# mymote-logger.net
KiCad netlist of a schematic drawn in EAGLE
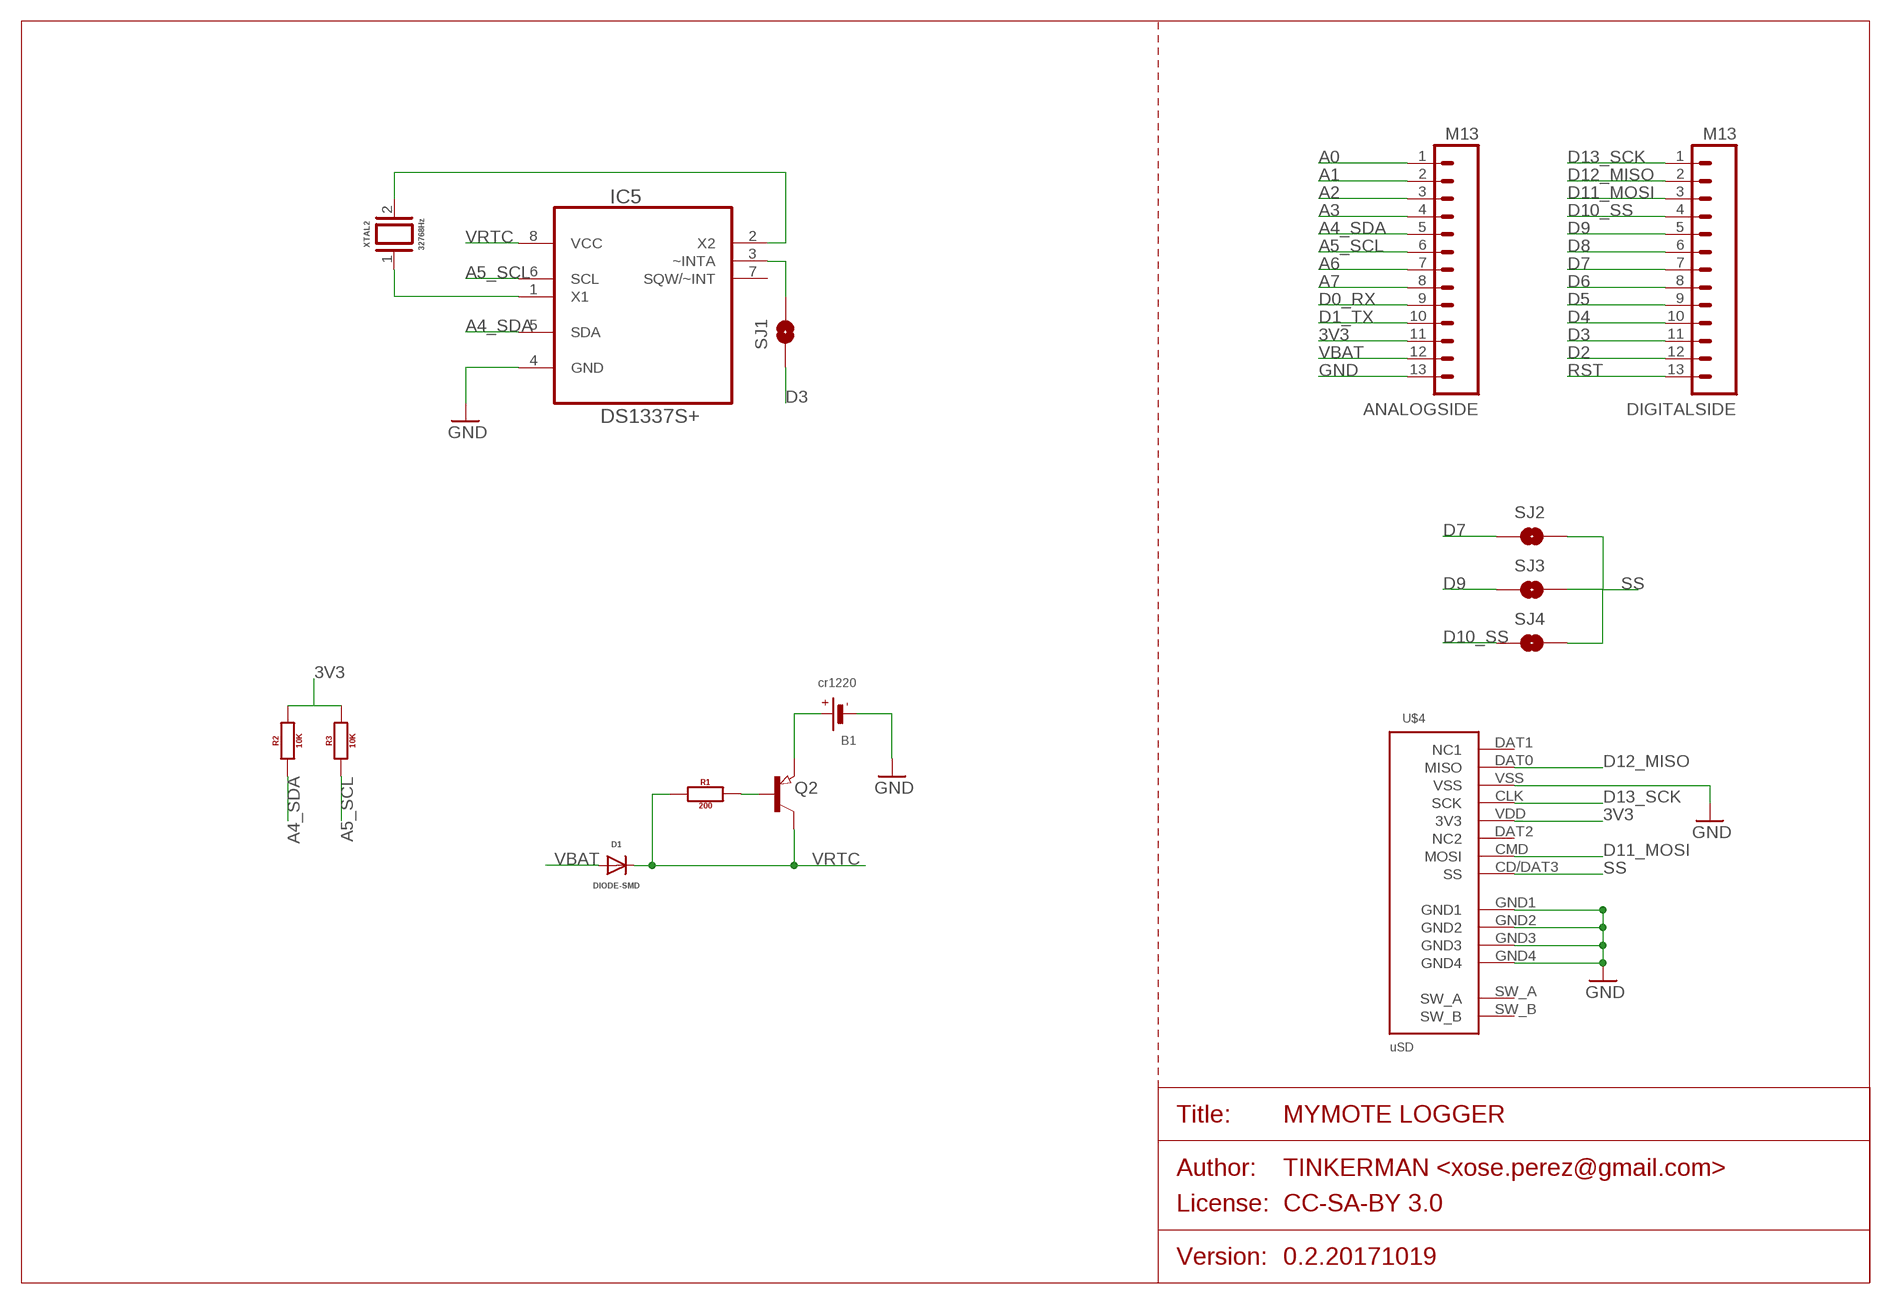
[diagram p0: schematic, sheet 1]

(export (version "E")
  (design (tool "Eeschema 10.0.6"))
  (components
    (comp (ref "ANALOGSIDE")
      (value "M13")
      (footprint "eagle-import:1X13_NO_SILK")
      (libsource (lib "eagle-import") (part "M13"))
    )
    (comp (ref "B1")
      (value "cr1220")
      (footprint "eagle-import:CR1220-2")
      (libsource (lib "eagle-import") (part "BATTERYCR1220_2"))
    )
    (comp (ref "D1")
      (value "DIODE-SMD")
      (footprint "eagle-import:0805_DIODE")
      (libsource (lib "eagle-import") (part "DIODE-SMD"))
    )
    (comp (ref "DIGITALSIDE")
      (value "M13")
      (footprint "eagle-import:1X13_NO_SILK")
      (libsource (lib "eagle-import") (part "M13"))
    )
    (comp (ref "IC5")
      (value "DS1337S+")
      (footprint "eagle-import:SOIC127P600X175-8N")
      (libsource (lib "eagle-import") (part "DS1337S+"))
    )
    (comp (ref "Q2")
      (value "PNP-TRANSISTOR_SOT23")
      (footprint "eagle-import:SOT23")
      (libsource (lib "eagle-import") (part "PNP-TRANSISTOR_SOT23"))
    )
    (comp (ref "R1")
      (value "200")
      (footprint "eagle-import:0805")
      (libsource (lib "eagle-import") (part "RESISTOR0805"))
    )
    (comp (ref "R2")
      (value "10K")
      (footprint "eagle-import:0805")
      (libsource (lib "eagle-import") (part "RESISTOR0805"))
    )
    (comp (ref "R3")
      (value "10K")
      (footprint "eagle-import:0805")
      (libsource (lib "eagle-import") (part "RESISTOR0805"))
    )
    (comp (ref "SJ1")
      (value "SOLDERJUMPERNO")
      (footprint "eagle-import:SJ_2S-NO")
      (libsource (lib "eagle-import") (part "SOLDERJUMPERNO"))
    )
    (comp (ref "SJ2")
      (value "SOLDERJUMPERNO")
      (footprint "eagle-import:SJ_2S-NO")
      (libsource (lib "eagle-import") (part "SOLDERJUMPERNO"))
    )
    (comp (ref "SJ3")
      (value "SOLDERJUMPERNO")
      (footprint "eagle-import:SJ_2S-NO")
      (libsource (lib "eagle-import") (part "SOLDERJUMPERNO"))
    )
    (comp (ref "SJ4")
      (value "SOLDERJUMPERNO")
      (footprint "eagle-import:SJ_2S-NO")
      (libsource (lib "eagle-import") (part "SOLDERJUMPERNO"))
    )
    (comp (ref "U$4")
      (value "uSD")
      (footprint "eagle-import:DM3D")
      (libsource (lib "eagle-import") (part "MICROSD"))
    )
    (comp (ref "XTAL2")
      (value "32768Hz")
      (footprint "eagle-import:TC38H")
      (libsource (lib "eagle-import") (part "CRYSTAL_TC38H"))
    )
  )
  (nets
    (net (code "1") (name "/3V3") (class "Default")
      (node (ref "ANALOGSIDE") (pin "11") (pinfunction "11_11") (pintype "passive"))
      (node (ref "R2") (pin "2") (pinfunction "2_2") (pintype "passive"))
      (node (ref "R3") (pin "2") (pinfunction "2_2") (pintype "passive"))
      (node (ref "U$4") (pin "VDD") (pinfunction "3V3_VDD") (pintype "bidirectional"))
    )
    (net (code "2") (name "/A0") (class "Default")
      (node (ref "ANALOGSIDE") (pin "1") (pinfunction "1_1") (pintype "passive"))
    )
    (net (code "3") (name "/A1") (class "Default")
      (node (ref "ANALOGSIDE") (pin "2") (pinfunction "2_2") (pintype "passive"))
    )
    (net (code "4") (name "/A2") (class "Default")
      (node (ref "ANALOGSIDE") (pin "3") (pinfunction "3_3") (pintype "passive"))
    )
    (net (code "5") (name "/A3") (class "Default")
      (node (ref "ANALOGSIDE") (pin "4") (pinfunction "4_4") (pintype "passive"))
    )
    (net (code "6") (name "/A4_SDA") (class "Default")
      (node (ref "ANALOGSIDE") (pin "5") (pinfunction "5_5") (pintype "passive"))
      (node (ref "IC5") (pin "5") (pinfunction "SDA_5") (pintype "bidirectional"))
      (node (ref "R2") (pin "1") (pinfunction "1_1") (pintype "passive"))
    )
    (net (code "7") (name "/A5_SCL") (class "Default")
      (node (ref "ANALOGSIDE") (pin "6") (pinfunction "6_6") (pintype "passive"))
      (node (ref "IC5") (pin "6") (pinfunction "SCL_6") (pintype "input"))
      (node (ref "R3") (pin "1") (pinfunction "1_1") (pintype "passive"))
    )
    (net (code "8") (name "/A6") (class "Default")
      (node (ref "ANALOGSIDE") (pin "7") (pinfunction "7_7") (pintype "passive"))
    )
    (net (code "9") (name "/A7") (class "Default")
      (node (ref "ANALOGSIDE") (pin "8") (pinfunction "8_8") (pintype "passive"))
    )
    (net (code "10") (name "/D0_RX") (class "Default")
      (node (ref "ANALOGSIDE") (pin "9") (pinfunction "9_9") (pintype "passive"))
    )
    (net (code "11") (name "/D1_TX") (class "Default")
      (node (ref "ANALOGSIDE") (pin "10") (pinfunction "10_10") (pintype "passive"))
    )
    (net (code "12") (name "/D2") (class "Default")
      (node (ref "DIGITALSIDE") (pin "12") (pinfunction "12_12") (pintype "passive"))
    )
    (net (code "13") (name "/D3") (class "Default")
      (node (ref "DIGITALSIDE") (pin "11") (pinfunction "11_11") (pintype "passive"))
      (node (ref "SJ1") (pin "1") (pinfunction "1_1") (pintype "passive"))
    )
    (net (code "14") (name "/D4") (class "Default")
      (node (ref "DIGITALSIDE") (pin "10") (pinfunction "10_10") (pintype "passive"))
    )
    (net (code "15") (name "/D5") (class "Default")
      (node (ref "DIGITALSIDE") (pin "9") (pinfunction "9_9") (pintype "passive"))
    )
    (net (code "16") (name "/D6") (class "Default")
      (node (ref "DIGITALSIDE") (pin "8") (pinfunction "8_8") (pintype "passive"))
    )
    (net (code "17") (name "/D7") (class "Default")
      (node (ref "DIGITALSIDE") (pin "7") (pinfunction "7_7") (pintype "passive"))
      (node (ref "SJ2") (pin "1") (pinfunction "1_1") (pintype "passive"))
    )
    (net (code "18") (name "/D8") (class "Default")
      (node (ref "DIGITALSIDE") (pin "6") (pinfunction "6_6") (pintype "passive"))
    )
    (net (code "19") (name "/D9") (class "Default")
      (node (ref "DIGITALSIDE") (pin "5") (pinfunction "5_5") (pintype "passive"))
      (node (ref "SJ3") (pin "1") (pinfunction "1_1") (pintype "passive"))
    )
    (net (code "20") (name "/D10_SS") (class "Default")
      (node (ref "DIGITALSIDE") (pin "4") (pinfunction "4_4") (pintype "passive"))
      (node (ref "SJ4") (pin "1") (pinfunction "1_1") (pintype "passive"))
    )
    (net (code "21") (name "/D11_MOSI") (class "Default")
      (node (ref "DIGITALSIDE") (pin "3") (pinfunction "3_3") (pintype "passive"))
      (node (ref "U$4") (pin "CMD") (pinfunction "MOSI_CMD") (pintype "bidirectional"))
    )
    (net (code "22") (name "/D12_MISO") (class "Default")
      (node (ref "DIGITALSIDE") (pin "2") (pinfunction "2_2") (pintype "passive"))
      (node (ref "U$4") (pin "DAT0") (pinfunction "MISO_DAT0") (pintype "bidirectional"))
    )
    (net (code "23") (name "/D13_SCK") (class "Default")
      (node (ref "DIGITALSIDE") (pin "1") (pinfunction "1_1") (pintype "passive"))
      (node (ref "U$4") (pin "CLK") (pinfunction "SCK_CLK") (pintype "bidirectional"))
    )
    (net (code "24") (name "/RST") (class "Default")
      (node (ref "DIGITALSIDE") (pin "13") (pinfunction "13_13") (pintype "passive"))
    )
    (net (code "25") (name "/SS") (class "Default")
      (node (ref "SJ2") (pin "2") (pinfunction "2_2") (pintype "passive"))
      (node (ref "SJ3") (pin "2") (pinfunction "2_2") (pintype "passive"))
      (node (ref "SJ4") (pin "2") (pinfunction "2_2") (pintype "passive"))
      (node (ref "U$4") (pin "CD/DAT3") (pinfunction "SS_CD/DAT3") (pintype "bidirectional"))
    )
    (net (code "26") (name "/VBAT") (class "Default")
      (node (ref "ANALOGSIDE") (pin "12") (pinfunction "12_12") (pintype "passive"))
      (node (ref "D1") (pin "A") (pinfunction "A_A") (pintype "passive"))
    )
    (net (code "27") (name "/VRTC") (class "Default")
      (node (ref "D1") (pin "C") (pinfunction "C_C") (pintype "passive"))
      (node (ref "IC5") (pin "8") (pinfunction "VCC_8") (pintype "power_in"))
      (node (ref "Q2") (pin "3") (pinfunction "C_3") (pintype "passive"))
      (node (ref "R1") (pin "1") (pinfunction "1_1") (pintype "passive"))
    )
    (net (code "28") (name "GND") (class "Default")
      (node (ref "ANALOGSIDE") (pin "13") (pinfunction "13_13") (pintype "passive"))
      (node (ref "B1") (pin "-") (pinfunction "-_-") (pintype "passive"))
      (node (ref "IC5") (pin "4") (pinfunction "GND_4") (pintype "passive"))
      (node (ref "U$4") (pin "GND1") (pinfunction "GND1_GND1") (pintype "bidirectional"))
      (node (ref "U$4") (pin "GND2") (pinfunction "GND2_GND2") (pintype "bidirectional"))
      (node (ref "U$4") (pin "GND3") (pinfunction "GND3_GND3") (pintype "bidirectional"))
      (node (ref "U$4") (pin "GND4") (pinfunction "GND4_GND4") (pintype "bidirectional"))
      (node (ref "U$4") (pin "VSS") (pinfunction "VSS_VSS") (pintype "bidirectional"))
    )
    (net (code "29") (name "Net-(IC5-X1)") (class "Default")
      (node (ref "IC5") (pin "1") (pinfunction "X1_1") (pintype "input"))
      (node (ref "XTAL2") (pin "1") (pinfunction "1_1") (pintype "passive"))
    )
    (net (code "30") (name "Net-(IC5-X2)") (class "Default")
      (node (ref "IC5") (pin "2") (pinfunction "X2_2") (pintype "passive"))
      (node (ref "XTAL2") (pin "2") (pinfunction "2_2") (pintype "passive"))
    )
    (net (code "31") (name "Net-(IC5-~{INTA})") (class "Default")
      (node (ref "IC5") (pin "3") (pinfunction "~{INTA}_3") (pintype "output"))
      (node (ref "SJ1") (pin "2") (pinfunction "2_2") (pintype "passive"))
    )
    (net (code "32") (name "Net-(Q2-B)") (class "Default")
      (node (ref "Q2") (pin "1") (pinfunction "B_1") (pintype "passive"))
      (node (ref "R1") (pin "2") (pinfunction "2_2") (pintype "passive"))
    )
    (net (code "33") (name "Net-(Q2-E)") (class "Default")
      (node (ref "B1") (pin "+") (pinfunction "+_+") (pintype "passive"))
      (node (ref "Q2") (pin "2") (pinfunction "E_2") (pintype "passive"))
    )
    (net (code "34") (name "unconnected-(IC5-SQW{slash}~{INT}-Pad7)") (class "Default")
      (node (ref "IC5") (pin "7") (pinfunction "SQW/~{INT}_7") (pintype "output"))
    )
    (net (code "35") (name "unconnected-(U$4-NC1-PadDAT1)") (class "Default")
      (node (ref "U$4") (pin "DAT1") (pinfunction "NC1_DAT1") (pintype "bidirectional"))
    )
    (net (code "36") (name "unconnected-(U$4-NC2-PadDAT2)") (class "Default")
      (node (ref "U$4") (pin "DAT2") (pinfunction "NC2_DAT2") (pintype "bidirectional"))
    )
    (net (code "37") (name "unconnected-(U$4-PadSW_A)") (class "Default")
      (node (ref "U$4") (pin "SW_A") (pinfunction "SW_A_SW_A") (pintype "bidirectional"))
    )
    (net (code "38") (name "unconnected-(U$4-PadSW_B)") (class "Default")
      (node (ref "U$4") (pin "SW_B") (pinfunction "SW_B_SW_B") (pintype "bidirectional"))
    )
  )
)
